# 8ChannelRebelSSR_v5.net
KiCad netlist of a schematic drawn in EAGLE
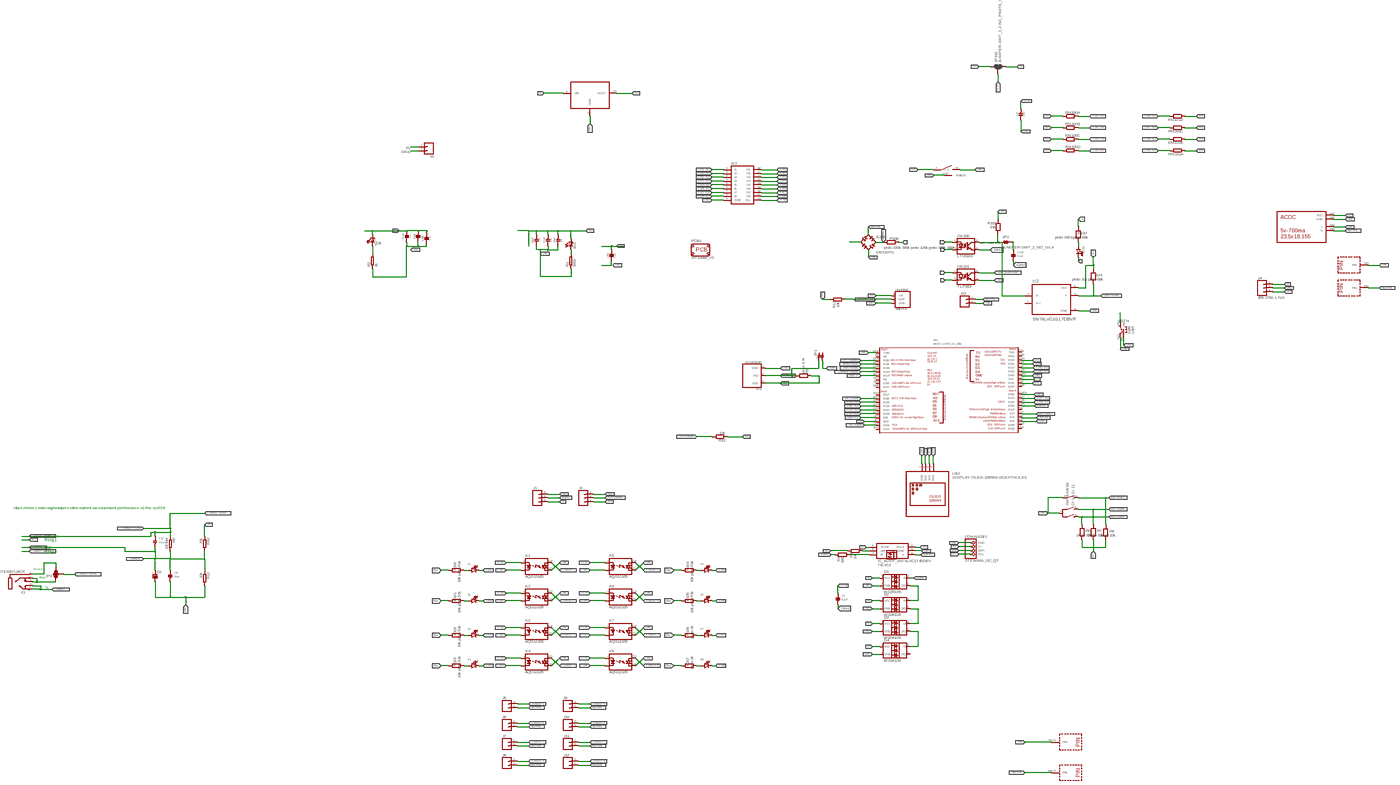
[diagram p0: schematic, sheet 1, overview]
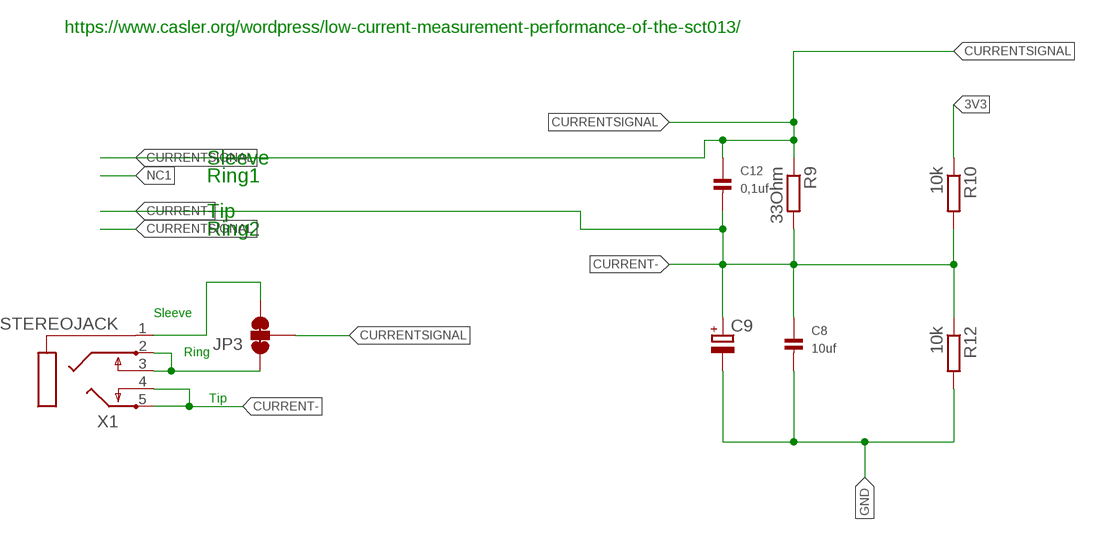
[diagram p1: schematic, sheet 1, part 1 of 4]
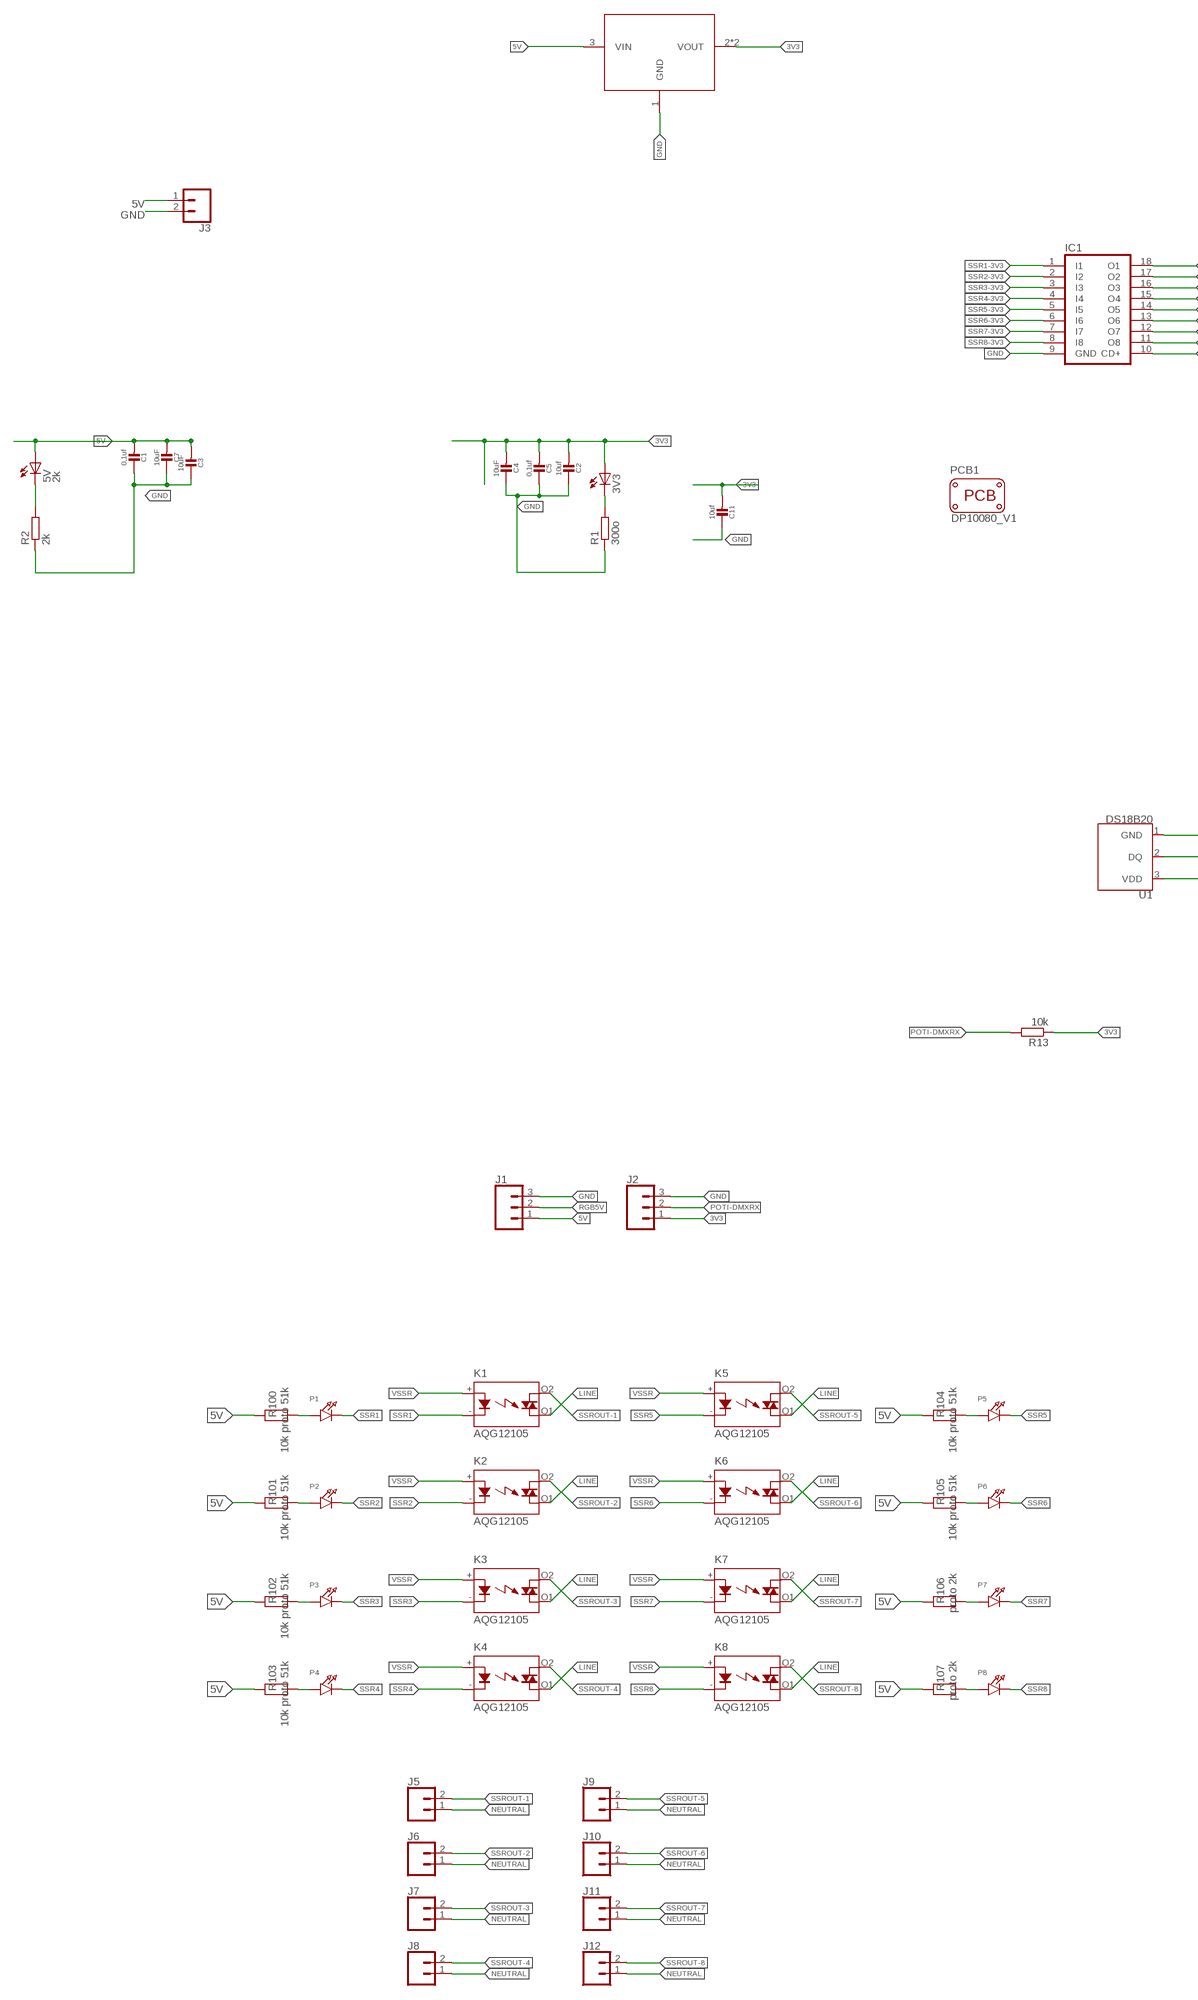
[diagram p2: schematic, sheet 1, part 2 of 4]
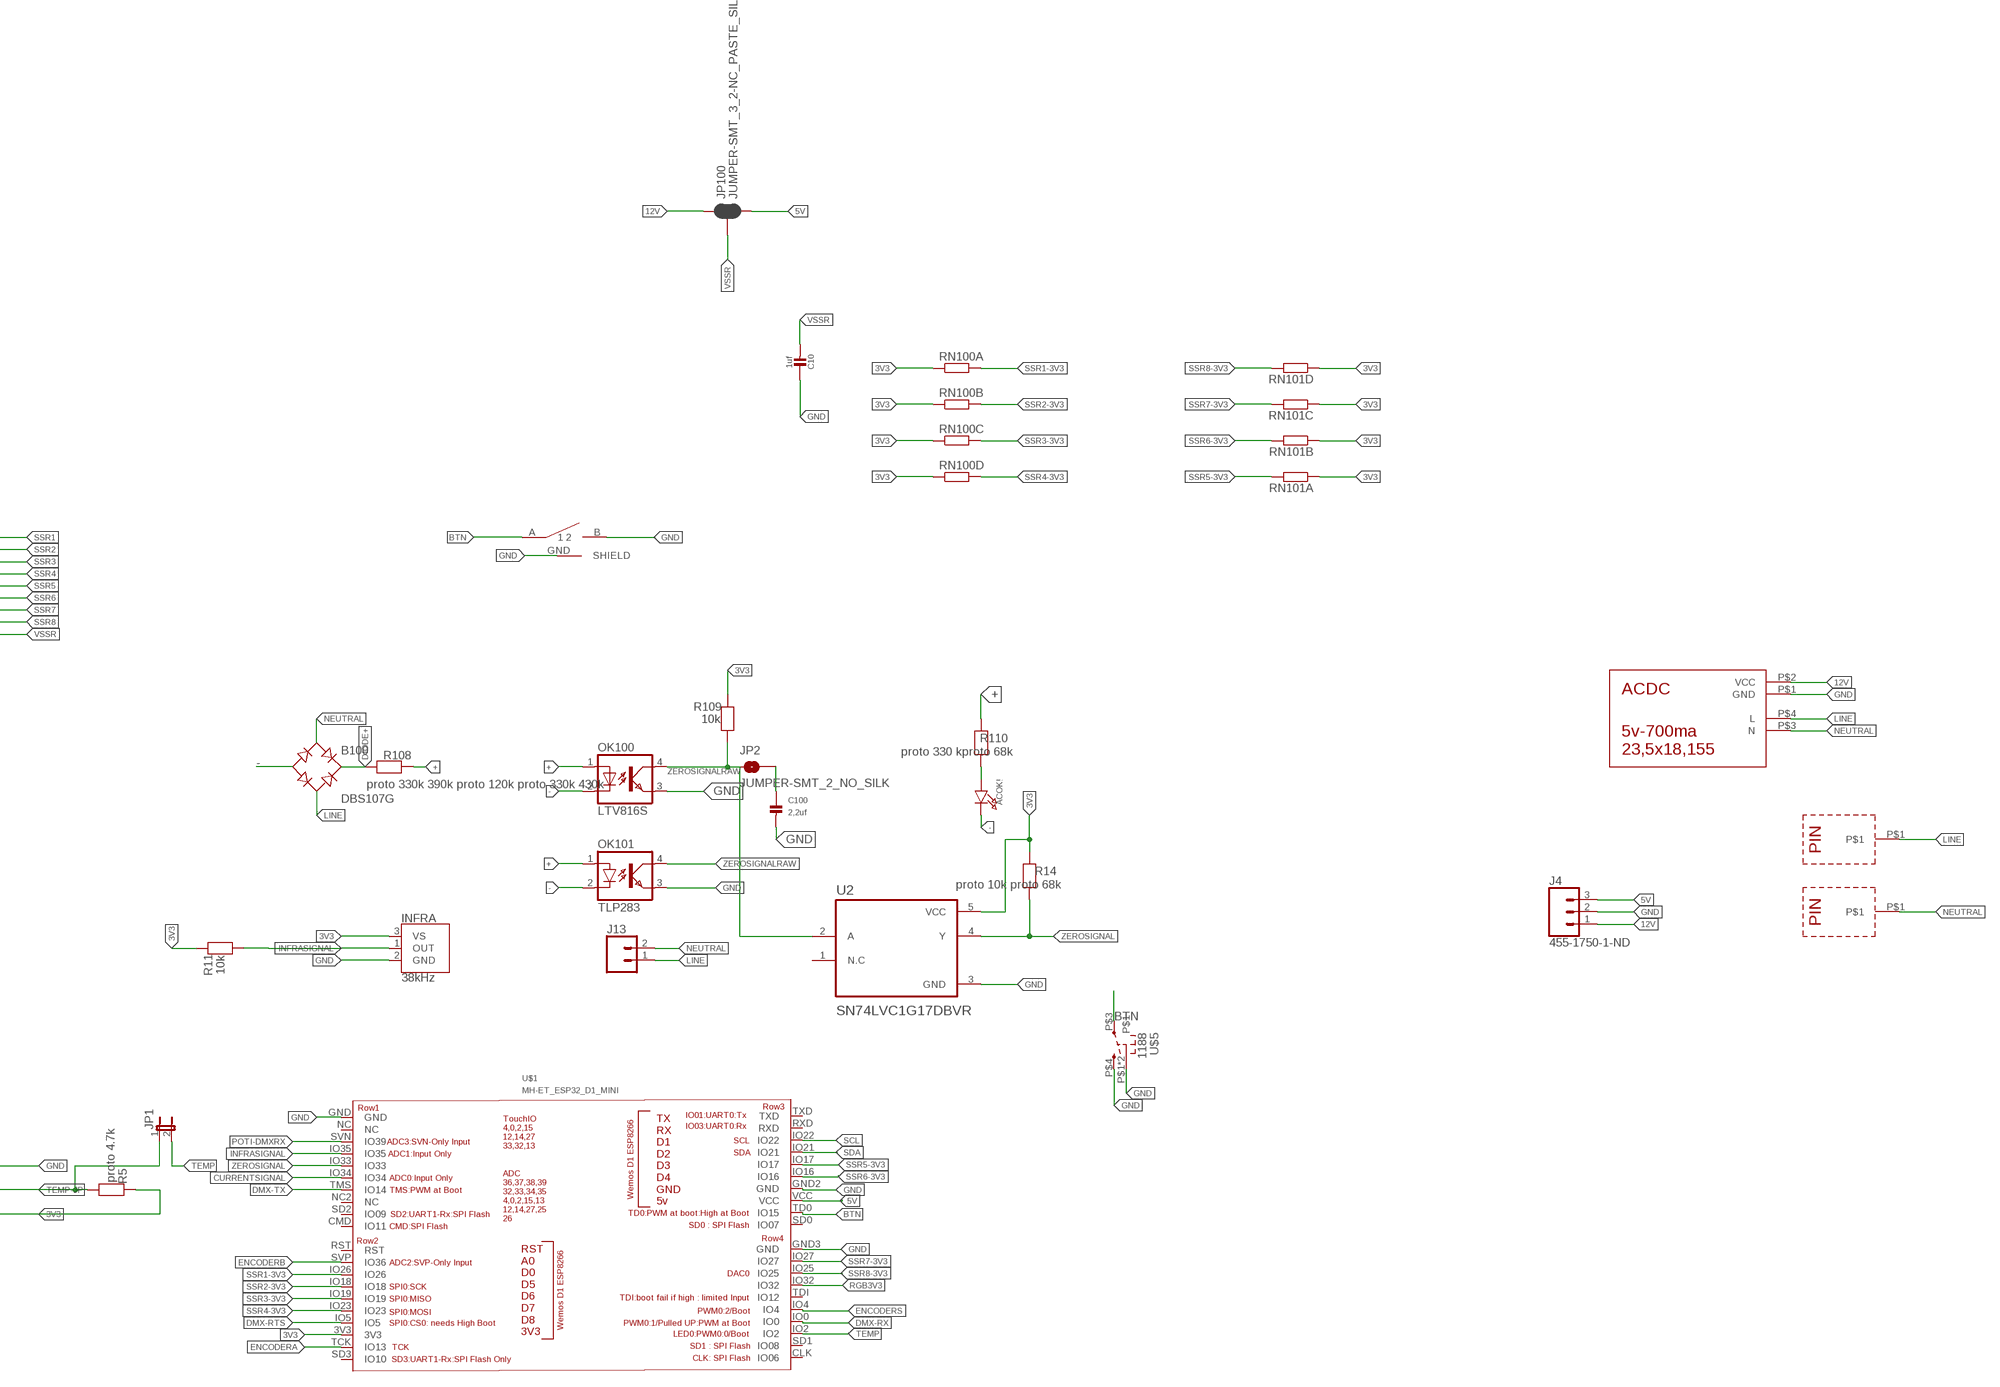
[diagram p3: schematic, sheet 1, part 3 of 4]
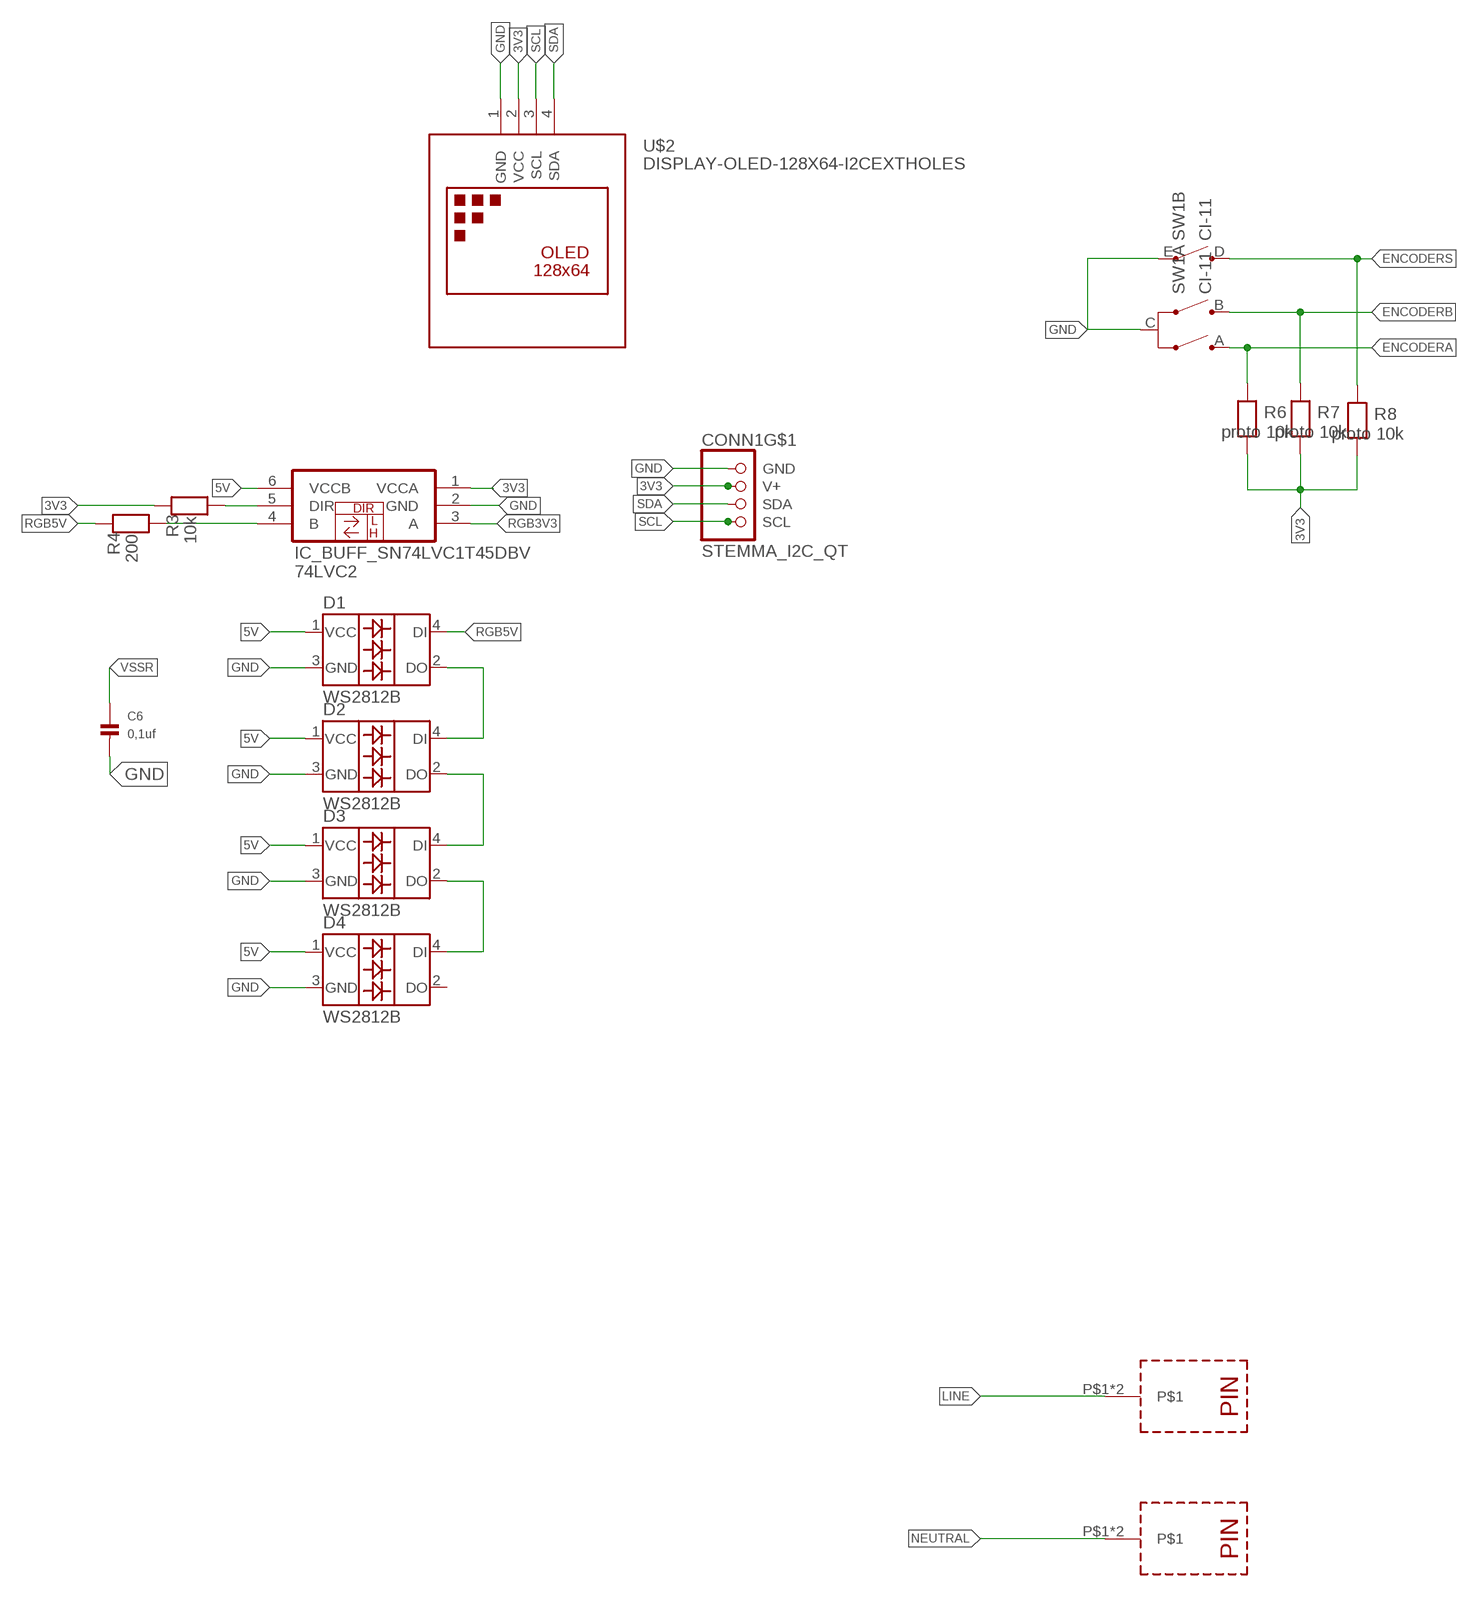
[diagram p4: schematic, sheet 1, part 4 of 4]

(export (version "E")
  (design (tool "Eeschema 10.0.6"))
  (components
    (comp (ref "3V3")
      (value "LEDCHIPLED_0805")
      (footprint "eagle-import:CHIPLED_0805")
      (libsource (lib "eagle-import") (part "LEDCHIPLED_0805"))
    )
    (comp (ref "5V")
      (value "2k")
      (footprint "eagle-import:CHIPLED_0805")
      (libsource (lib "eagle-import") (part "LEDCHIPLED_0805"))
    )
    (comp (ref "74LVC2")
      (value "IC_BUFF_SN74LVC1T45DBV")
      (footprint "eagle-import:DBV-R-PDSO-G6")
      (libsource (lib "eagle-import") (part "IC_BUFF_SN74LVC1T45DBV"))
    )
    (comp (ref "ACOK!")
      (value "LED0805")
      (footprint "eagle-import:CHIPLED_0805")
      (libsource (lib "eagle-import") (part "LED0805"))
    )
    (comp (ref "B100")
      (value "DBS107G")
      (footprint "eagle-import:DBS")
      (libsource (lib "eagle-import") (part "DB?GS107"))
    )
    (comp (ref "C1")
      (value "0,1uf")
      (footprint "eagle-import:0805-NO")
      (libsource (lib "eagle-import") (part "CAP_CERAMIC0805-NOOUTLINE"))
    )
    (comp (ref "C2")
      (value "10uf")
      (footprint "eagle-import:0805-NO")
      (libsource (lib "eagle-import") (part "CAP_CERAMIC0805-NOOUTLINE"))
    )
    (comp (ref "C3")
      (value "10uF")
      (footprint "eagle-import:0805-NO")
      (libsource (lib "eagle-import") (part "CAP_CERAMIC0805-NOOUTLINE"))
    )
    (comp (ref "C4")
      (value "10uF")
      (footprint "eagle-import:0805-NO")
      (libsource (lib "eagle-import") (part "CAP_CERAMIC0805-NOOUTLINE"))
    )
    (comp (ref "C5")
      (value "0,1uf")
      (footprint "eagle-import:0805-NO")
      (libsource (lib "eagle-import") (part "CAP_CERAMIC0805-NOOUTLINE"))
    )
    (comp (ref "C6")
      (value "0,1uf")
      (footprint "eagle-import:0805_NOTHERMALS@1")
      (libsource (lib "eagle-import") (part "CAP_CERAMIC0805-NOTHERMALS"))
    )
    (comp (ref "C7")
      (value "10uF")
      (footprint "eagle-import:0805-NO")
      (libsource (lib "eagle-import") (part "CAP_CERAMIC0805-NOOUTLINE"))
    )
    (comp (ref "C8")
      (value "10uf")
      (footprint "eagle-import:0805_NOTHERMALS@1")
      (libsource (lib "eagle-import") (part "CAP_CERAMIC0805-NOTHERMALS"))
    )
    (comp (ref "C9")
      (value "CPOL-EUE1.8-4")
      (footprint "eagle-import:E1,8-4")
      (libsource (lib "eagle-import") (part "CPOL-EUE1.8-4"))
    )
    (comp (ref "C10")
      (value "1uf")
      (footprint "eagle-import:0805-NO")
      (libsource (lib "eagle-import") (part "CAP_CERAMIC0805-NOOUTLINE"))
    )
    (comp (ref "C11")
      (value "10uf")
      (footprint "eagle-import:0805-NO")
      (libsource (lib "eagle-import") (part "CAP_CERAMIC0805-NOOUTLINE"))
    )
    (comp (ref "C12")
      (value "0,1uf")
      (footprint "eagle-import:0805_NOTHERMALS@1")
      (libsource (lib "eagle-import") (part "CAP_CERAMIC0805-NOTHERMALS"))
    )
    (comp (ref "C100")
      (value "2,2uf")
      (footprint "eagle-import:0805_NOTHERMALS@1")
      (libsource (lib "eagle-import") (part "CAP_CERAMIC0805-NOTHERMALS"))
    )
    (comp (ref "CONN1")
      (value "STEMMA_I2C_QT")
      (footprint "eagle-import:JST_SH4")
      (libsource (lib "eagle-import") (part "STEMMA_I2C_QT"))
    )
    (comp (ref "D1")
      (value "WS2812B")
      (footprint "eagle-import:WS2812B")
      (libsource (lib "eagle-import") (part "WS2812B"))
    )
    (comp (ref "D2")
      (value "WS2812B")
      (footprint "eagle-import:WS2812B")
      (libsource (lib "eagle-import") (part "WS2812B"))
    )
    (comp (ref "D3")
      (value "WS2812B")
      (footprint "eagle-import:WS2812B")
      (libsource (lib "eagle-import") (part "WS2812B"))
    )
    (comp (ref "D4")
      (value "WS2812B")
      (footprint "eagle-import:WS2812B")
      (libsource (lib "eagle-import") (part "WS2812B"))
    )
    (comp (ref "IC1")
      (value "IC_ULN2803ADW")
      (footprint "eagle-import:SO-18L")
      (libsource (lib "eagle-import") (part "IC_ULN2803ADW"))
    )
    (comp (ref "INFRA")
      (value "38kHz")
      (footprint "eagle-import:TSOP382")
      (libsource (lib "eagle-import") (part "TSOP38238"))
    )
    (comp (ref "J1")
      (value "CONN_03POLAR")
      (footprint "eagle-import:MOLEX-1X3")
      (libsource (lib "eagle-import") (part "CONN_03POLAR"))
    )
    (comp (ref "J2")
      (value "CONN_03POLAR")
      (footprint "eagle-import:MOLEX-1X3")
      (libsource (lib "eagle-import") (part "CONN_03POLAR"))
    )
    (comp (ref "J3")
      (value "CONN_02POLAR")
      (footprint "eagle-import:MOLEX-1X2")
      (libsource (lib "eagle-import") (part "CONN_02POLAR"))
    )
    (comp (ref "J4")
      (value "455-1750-1-ND")
      (footprint "eagle-import:1X03")
      (libsource (lib "eagle-import") (part "CONN_03"))
    )
    (comp (ref "J5")
      (value "CONN_023.5MM")
      (footprint "eagle-import:SCREWTERMINAL-3.5MM-2")
      (libsource (lib "eagle-import") (part "CONN_023.5MM"))
    )
    (comp (ref "J6")
      (value "CONN_023.5MM")
      (footprint "eagle-import:SCREWTERMINAL-3.5MM-2")
      (libsource (lib "eagle-import") (part "CONN_023.5MM"))
    )
    (comp (ref "J7")
      (value "CONN_023.5MM")
      (footprint "eagle-import:SCREWTERMINAL-3.5MM-2")
      (libsource (lib "eagle-import") (part "CONN_023.5MM"))
    )
    (comp (ref "J8")
      (value "CONN_023.5MM")
      (footprint "eagle-import:SCREWTERMINAL-3.5MM-2")
      (libsource (lib "eagle-import") (part "CONN_023.5MM"))
    )
    (comp (ref "J9")
      (value "CONN_023.5MM")
      (footprint "eagle-import:SCREWTERMINAL-3.5MM-2")
      (libsource (lib "eagle-import") (part "CONN_023.5MM"))
    )
    (comp (ref "J10")
      (value "CONN_023.5MM")
      (footprint "eagle-import:SCREWTERMINAL-3.5MM-2")
      (libsource (lib "eagle-import") (part "CONN_023.5MM"))
    )
    (comp (ref "J11")
      (value "CONN_023.5MM")
      (footprint "eagle-import:SCREWTERMINAL-3.5MM-2")
      (libsource (lib "eagle-import") (part "CONN_023.5MM"))
    )
    (comp (ref "J12")
      (value "CONN_023.5MM")
      (footprint "eagle-import:SCREWTERMINAL-3.5MM-2")
      (libsource (lib "eagle-import") (part "CONN_023.5MM"))
    )
    (comp (ref "J13")
      (value "CONN_023.5MM")
      (footprint "eagle-import:SCREWTERMINAL-3.5MM-2")
      (libsource (lib "eagle-import") (part "CONN_023.5MM"))
    )
    (comp (ref "JP1")
      (value "JUMPER2")
      (footprint "eagle-import:JUMPER2")
      (libsource (lib "eagle-import") (part "JUMPER2"))
    )
    (comp (ref "JP2")
      (value "JUMPER-SMT_2_NO_SILK")
      (footprint "eagle-import:SMT-JUMPER_2_NO_SILK")
      (libsource (lib "eagle-import") (part "JUMPER-SMT_2_NO_SILK"))
    )
    (comp (ref "JP3")
      (value "JUMPER-PAD-3-NC_BY_TRACE")
      (footprint "eagle-import:PAD-JUMPER-3-3OF3_NC_BY_TRACE_YES_SILK_FULL_BOX")
      (libsource (lib "eagle-import") (part "JUMPER-PAD-3-NC_BY_TRACE"))
    )
    (comp (ref "JP100")
      (value "JUMPER-SMT_3_2-NC_PASTE_SILK")
      (footprint "eagle-import:SMT-JUMPER_3_2-NC_PASTE_SILK")
      (libsource (lib "eagle-import") (part "JUMPER-SMT_3_2-NC_PASTE_SILK"))
    )
    (comp (ref "K1")
      (value "AQG12105")
      (footprint "eagle-import:AQG")
      (fields (field (name "MF") "AROMAT/ MATSUSHITA"))
      (libsource (lib "eagle-import") (part "AQG12105"))
    )
    (comp (ref "K2")
      (value "AQG12105")
      (footprint "eagle-import:AQG")
      (fields (field (name "MF") "AROMAT/ MATSUSHITA"))
      (libsource (lib "eagle-import") (part "AQG12105"))
    )
    (comp (ref "K3")
      (value "AQG12105")
      (footprint "eagle-import:AQG")
      (fields (field (name "MF") "AROMAT/ MATSUSHITA"))
      (libsource (lib "eagle-import") (part "AQG12105"))
    )
    (comp (ref "K4")
      (value "AQG12105")
      (footprint "eagle-import:AQG")
      (fields (field (name "MF") "AROMAT/ MATSUSHITA"))
      (libsource (lib "eagle-import") (part "AQG12105"))
    )
    (comp (ref "K5")
      (value "AQG12105")
      (footprint "eagle-import:AQG")
      (fields (field (name "MF") "AROMAT/ MATSUSHITA"))
      (libsource (lib "eagle-import") (part "AQG12105"))
    )
    (comp (ref "K6")
      (value "AQG12105")
      (footprint "eagle-import:AQG")
      (fields (field (name "MF") "AROMAT/ MATSUSHITA"))
      (libsource (lib "eagle-import") (part "AQG12105"))
    )
    (comp (ref "K7")
      (value "AQG12105")
      (footprint "eagle-import:AQG")
      (fields (field (name "MF") "AROMAT/ MATSUSHITA"))
      (libsource (lib "eagle-import") (part "AQG12105"))
    )
    (comp (ref "K8")
      (value "AQG12105")
      (footprint "eagle-import:AQG")
      (fields (field (name "MF") "AROMAT/ MATSUSHITA"))
      (libsource (lib "eagle-import") (part "AQG12105"))
    )
    (comp (ref "OK100")
      (value "LTV816S")
      (footprint "eagle-import:DIL4-SMD")
      (libsource (lib "eagle-import") (part "LTV816S"))
    )
    (comp (ref "OK101")
      (value "TLP283")
      (footprint "eagle-import:MINI-FLAT-4")
      (libsource (lib "eagle-import") (part "TLP283"))
    )
    (comp (ref "P1")
      (value "LED0805")
      (footprint "eagle-import:CHIPLED_0805")
      (libsource (lib "eagle-import") (part "LED0805"))
    )
    (comp (ref "P2")
      (value "LED0805")
      (footprint "eagle-import:CHIPLED_0805")
      (libsource (lib "eagle-import") (part "LED0805"))
    )
    (comp (ref "P3")
      (value "LED0805")
      (footprint "eagle-import:CHIPLED_0805")
      (libsource (lib "eagle-import") (part "LED0805"))
    )
    (comp (ref "P4")
      (value "LED0805")
      (footprint "eagle-import:CHIPLED_0805")
      (libsource (lib "eagle-import") (part "LED0805"))
    )
    (comp (ref "P5")
      (value "LED0805")
      (footprint "eagle-import:CHIPLED_0805")
      (libsource (lib "eagle-import") (part "LED0805"))
    )
    (comp (ref "P6")
      (value "LED0805")
      (footprint "eagle-import:CHIPLED_0805")
      (libsource (lib "eagle-import") (part "LED0805"))
    )
    (comp (ref "P7")
      (value "LED0805")
      (footprint "eagle-import:CHIPLED_0805")
      (libsource (lib "eagle-import") (part "LED0805"))
    )
    (comp (ref "P8")
      (value "LED0805")
      (footprint "eagle-import:CHIPLED_0805")
      (libsource (lib "eagle-import") (part "LED0805"))
    )
    (comp (ref "PCB1")
      (value "PCB_DP_RECTANGLE-80X100")
      (footprint "eagle-import:DP10080_V1")
      (fields (field (name "PCB_SIZE") "DP10080_V1"))
      (libsource (lib "eagle-import") (part "PCB_DP_RECTANGLE-80X100"))
    )
    (comp (ref "R1")
      (value "300o")
      (footprint "eagle-import:R805")
      (libsource (lib "eagle-import") (part "RESISTOR-0805R805"))
    )
    (comp (ref "R2")
      (value "2k")
      (footprint "eagle-import:R805")
      (libsource (lib "eagle-import") (part "RESISTOR-0805R805"))
    )
    (comp (ref "R3")
      (value "10k")
      (footprint "eagle-import:0805@1")
      (libsource (lib "eagle-import") (part "RESISTOR0805"))
    )
    (comp (ref "R4")
      (value "200")
      (footprint "eagle-import:0805@1")
      (libsource (lib "eagle-import") (part "RESISTOR0805"))
    )
    (comp (ref "R5")
      (value "proto 4.7k")
      (footprint "eagle-import:0805@1")
      (libsource (lib "eagle-import") (part "RESISTOR0805"))
    )
    (comp (ref "R6")
      (value "proto 10k")
      (footprint "eagle-import:0805@1")
      (libsource (lib "eagle-import") (part "RESISTOR0805"))
    )
    (comp (ref "R7")
      (value "proto 10k")
      (footprint "eagle-import:0805@1")
      (libsource (lib "eagle-import") (part "RESISTOR0805"))
    )
    (comp (ref "R8")
      (value "proto 10k")
      (footprint "eagle-import:0805@1")
      (libsource (lib "eagle-import") (part "RESISTOR0805"))
    )
    (comp (ref "R9")
      (value "33Ohm")
      (footprint "eagle-import:R805")
      (libsource (lib "eagle-import") (part "RESISTOR-0805R805"))
    )
    (comp (ref "R10")
      (value "10k")
      (footprint "eagle-import:R805")
      (libsource (lib "eagle-import") (part "RESISTOR-0805R805"))
    )
    (comp (ref "R11")
      (value "10k")
      (footprint "eagle-import:0805@1")
      (libsource (lib "eagle-import") (part "RESISTOR0805"))
    )
    (comp (ref "R12")
      (value "10k")
      (footprint "eagle-import:R805")
      (libsource (lib "eagle-import") (part "RESISTOR-0805R805"))
    )
    (comp (ref "R13")
      (value "10k")
      (footprint "eagle-import:R805")
      (libsource (lib "eagle-import") (part "RESISTOR-0805R805"))
    )
    (comp (ref "R14")
      (value "proto 10k proto 68k")
      (footprint "eagle-import:0805@1")
      (libsource (lib "eagle-import") (part "RESISTOR0805"))
    )
    (comp (ref "R100")
      (value "10k proto 51k")
      (footprint "eagle-import:0805@1")
      (libsource (lib "eagle-import") (part "RESISTOR0805"))
    )
    (comp (ref "R101")
      (value "10k proto 51k")
      (footprint "eagle-import:0805@1")
      (libsource (lib "eagle-import") (part "RESISTOR0805"))
    )
    (comp (ref "R102")
      (value "10k proto 51k")
      (footprint "eagle-import:0805@1")
      (libsource (lib "eagle-import") (part "RESISTOR0805"))
    )
    (comp (ref "R103")
      (value "10k proto 51k")
      (footprint "eagle-import:0805@1")
      (libsource (lib "eagle-import") (part "RESISTOR0805"))
    )
    (comp (ref "R104")
      (value "10k proto 51k")
      (footprint "eagle-import:0805@1")
      (libsource (lib "eagle-import") (part "RESISTOR0805"))
    )
    (comp (ref "R105")
      (value "10k proto 51k")
      (footprint "eagle-import:0805@1")
      (libsource (lib "eagle-import") (part "RESISTOR0805"))
    )
    (comp (ref "R106")
      (value "proto 2k")
      (footprint "eagle-import:0805@1")
      (libsource (lib "eagle-import") (part "RESISTOR0805"))
    )
    (comp (ref "R107")
      (value "proto 2k")
      (footprint "eagle-import:0805@1")
      (libsource (lib "eagle-import") (part "RESISTOR0805"))
    )
    (comp (ref "R108")
      (value "proto 330k 390k proto 120k proto 330k 430k")
      (footprint "eagle-import:0805@1")
      (libsource (lib "eagle-import") (part "RESISTOR0805"))
    )
    (comp (ref "R109")
      (value "10k")
      (footprint "eagle-import:0805@1")
      (libsource (lib "eagle-import") (part "RESISTOR0805"))
    )
    (comp (ref "R110")
      (value "proto 330 kproto 68k")
      (footprint "eagle-import:0805@1")
      (libsource (lib "eagle-import") (part "RESISTOR0805"))
    )
    (comp (ref "RN100")
      (value "RESISTOR_ARRAY_4")
      (footprint "eagle-import:RN8P-4R-CRA06S")
      (libsource (lib "eagle-import") (part "RESISTOR_ARRAY_4"))
    )
    (comp (ref "RN101")
      (value "RESISTOR_ARRAY_4")
      (footprint "eagle-import:RN8P-4R-CRA06S")
      (libsource (lib "eagle-import") (part "RESISTOR_ARRAY_4"))
    )
    (comp (ref "SW1")
      (value "CI-11")
      (footprint "eagle-import:CI-11")
      (libsource (lib "eagle-import") (part "CI-11"))
    )
    (comp (ref "U$1")
      (value "MH-ET_ESP32_D1_MINI")
      (footprint "eagle-import:MH-ET_ESP32_D1_MINI")
      (libsource (lib "eagle-import") (part "MH-ET_ESP32_D1_MINI"))
    )
    (comp (ref "U$2")
      (value "DISPLAY-OLED-128X64-I2CEXTHOLES")
      (footprint "eagle-import:DISPLAY-OLED-128X64-MAX-I2C")
      (libsource (lib "eagle-import") (part "DISPLAY-OLED-128X64-I2CEXTHOLES"))
    )
    (comp (ref "U$4")
      (value "SWITCH4.5-4,5")
      (footprint "eagle-import:SWITCH4.5X4.5")
      (libsource (lib "eagle-import") (part "SWITCH4.5-4,5"))
    )
    (comp (ref "U$5")
      (value "1188")
      (footprint "eagle-import:1188")
      (libsource (lib "eagle-import") (part "1188"))
    )
    (comp (ref "U$6")
      (value "AP11173V3")
      (footprint "eagle-import:SOT223")
      (libsource (lib "eagle-import") (part "AP11173V3"))
    )
    (comp (ref "U$7")
      (value "ACDC-SUPPLY")
      (footprint "eagle-import:ACDC-5V")
      (libsource (lib "eagle-import") (part "ACDC-SUPPLY"))
    )
    (comp (ref "U$15")
      (value "EST026_COLDPRESSTERMINAL")
      (footprint "eagle-import:EST026-COLDPRESSTERMINAL")
      (libsource (lib "eagle-import") (part "EST026_COLDPRESSTERMINAL"))
    )
    (comp (ref "U$16")
      (value "SCREWTERMINAL_BLOCL5X5_FLAT")
      (footprint "eagle-import:SCREWTERMINALFLAT5X5")
      (libsource (lib "eagle-import") (part "SCREWTERMINAL_BLOCL5X5_FLAT"))
    )
    (comp (ref "U$17")
      (value "EST026_COLDPRESSTERMINAL")
      (footprint "eagle-import:EST026-COLDPRESSTERMINAL")
      (libsource (lib "eagle-import") (part "EST026_COLDPRESSTERMINAL"))
    )
    (comp (ref "U$18")
      (value "SCREWTERMINAL_BLOCL5X5_FLAT")
      (footprint "eagle-import:SCREWTERMINALFLAT5X5")
      (libsource (lib "eagle-import") (part "SCREWTERMINAL_BLOCL5X5_FLAT"))
    )
    (comp (ref "U1")
      (value "DS18B20")
      (footprint "eagle-import:TO-92-AMMO")
      (libsource (lib "eagle-import") (part "DS18B20"))
    )
    (comp (ref "U2")
      (value "SN74LVC1G17DBVR")
      (footprint "eagle-import:SOT95P280X145-5N")
      (fields (field (name "MF") "Texas Instruments"))
      (libsource (lib "eagle-import") (part "SN74LVC1G17DBVR"))
    )
    (comp (ref "X1")
      (value "STEREOJACK")
      (footprint "eagle-import:STX3100")
      (libsource (lib "eagle-import") (part "STEREOJACK"))
    )
  )
  (nets
    (net (code "1") (name "+") (class "Default")
      (node (ref "OK100") (pin "1") (pinfunction "A_1") (pintype "passive"))
      (node (ref "OK101") (pin "1") (pinfunction "A_1") (pintype "passive"))
      (node (ref "R108") (pin "2") (pinfunction "2_2") (pintype "passive"))
      (node (ref "R110") (pin "2") (pinfunction "2_2") (pintype "passive"))
    )
    (net (code "2") (name "-") (class "Default")
      (node (ref "ACOK!") (pin "C") (pinfunction "C_C") (pintype "passive"))
      (node (ref "B100") (pin "-") (pinfunction "-_-") (pintype "passive"))
      (node (ref "OK100") (pin "2") (pinfunction "C_2") (pintype "passive"))
      (node (ref "OK101") (pin "2") (pinfunction "C_2") (pintype "passive"))
    )
    (net (code "3") (name "3V3") (class "Default")
      (node (ref "3V3") (pin "A") (pinfunction "A_A") (pintype "passive"))
      (node (ref "74LVC2") (pin "1") (pinfunction "VCCA_1") (pintype "power_in"))
      (node (ref "C11") (pin "2") (pinfunction "2_2") (pintype "passive"))
      (node (ref "C2") (pin "2") (pinfunction "2_2") (pintype "passive"))
      (node (ref "C4") (pin "2") (pinfunction "2_2") (pintype "passive"))
      (node (ref "C5") (pin "2") (pinfunction "2_2") (pintype "passive"))
      (node (ref "CONN1") (pin "2") (pinfunction "V+_2") (pintype "passive"))
      (node (ref "INFRA") (pin "3") (pinfunction "VS_3") (pintype "bidirectional"))
      (node (ref "J2") (pin "1") (pinfunction "1_1") (pintype "passive"))
      (node (ref "R10") (pin "1") (pinfunction "1_1") (pintype "passive"))
      (node (ref "R109") (pin "2") (pinfunction "2_2") (pintype "passive"))
      (node (ref "R11") (pin "2") (pinfunction "2_2") (pintype "passive"))
      (node (ref "R13") (pin "1") (pinfunction "1_1") (pintype "passive"))
      (node (ref "R14") (pin "2") (pinfunction "2_2") (pintype "passive"))
      (node (ref "R3") (pin "2") (pinfunction "2_2") (pintype "passive"))
      (node (ref "R5") (pin "2") (pinfunction "2_2") (pintype "passive"))
      (node (ref "R6") (pin "1") (pinfunction "1_1") (pintype "passive"))
      (node (ref "R7") (pin "1") (pinfunction "1_1") (pintype "passive"))
      (node (ref "R8") (pin "1") (pinfunction "1_1") (pintype "passive"))
      (node (ref "RN100") (pin "1") (pinfunction "1_1") (pintype "passive"))
      (node (ref "RN100") (pin "2") (pinfunction "1_2") (pintype "passive"))
      (node (ref "RN100") (pin "3") (pinfunction "1_3") (pintype "passive"))
      (node (ref "RN100") (pin "4") (pinfunction "1_4") (pintype "passive"))
      (node (ref "RN101") (pin "1") (pinfunction "1_1") (pintype "passive"))
      (node (ref "RN101") (pin "2") (pinfunction "1_2") (pintype "passive"))
      (node (ref "RN101") (pin "3") (pinfunction "1_3") (pintype "passive"))
      (node (ref "RN101") (pin "4") (pinfunction "1_4") (pintype "passive"))
      (node (ref "U$1") (pin "3V3") (pinfunction "3V3_3V3") (pintype "bidirectional"))
      (node (ref "U$2") (pin "2") (pinfunction "VCC_2") (pintype "power_in"))
      (node (ref "U$6") (pin "2") (pinfunction "VOUT_2") (pintype "bidirectional"))
      (node (ref "U$6") (pin "4") (pinfunction "VOUT_4") (pintype "bidirectional"))
      (node (ref "U1") (pin "3") (pinfunction "VDD_3") (pintype "power_in"))
      (node (ref "U2") (pin "5") (pinfunction "VCC_5") (pintype "power_in"))
    )
    (net (code "4") (name "5V") (class "Default")
      (node (ref "5V") (pin "A") (pinfunction "A_A") (pintype "passive"))
      (node (ref "74LVC2") (pin "6") (pinfunction "VCCB_6") (pintype "power_in"))
      (node (ref "C1") (pin "2") (pinfunction "2_2") (pintype "passive"))
      (node (ref "C3") (pin "2") (pinfunction "2_2") (pintype "passive"))
      (node (ref "C7") (pin "2") (pinfunction "2_2") (pintype "passive"))
      (node (ref "D1") (pin "1") (pinfunction "VCC_1") (pintype "power_in"))
      (node (ref "D2") (pin "1") (pinfunction "VCC_1") (pintype "power_in"))
      (node (ref "D3") (pin "1") (pinfunction "VCC_1") (pintype "power_in"))
      (node (ref "D4") (pin "1") (pinfunction "VCC_1") (pintype "power_in"))
      (node (ref "J1") (pin "1") (pinfunction "1_1") (pintype "passive"))
      (node (ref "J3") (pin "1") (pinfunction "1_1") (pintype "passive"))
      (node (ref "J4") (pin "3") (pinfunction "3_3") (pintype "passive"))
      (node (ref "JP100") (pin "3") (pinfunction "3_3") (pintype "passive"))
      (node (ref "R100") (pin "2") (pinfunction "2_2") (pintype "passive"))
      (node (ref "R101") (pin "2") (pinfunction "2_2") (pintype "passive"))
      (node (ref "R102") (pin "2") (pinfunction "2_2") (pintype "passive"))
      (node (ref "R103") (pin "2") (pinfunction "2_2") (pintype "passive"))
      (node (ref "R104") (pin "2") (pinfunction "2_2") (pintype "passive"))
      (node (ref "R105") (pin "2") (pinfunction "2_2") (pintype "passive"))
      (node (ref "R106") (pin "2") (pinfunction "2_2") (pintype "passive"))
      (node (ref "R107") (pin "2") (pinfunction "2_2") (pintype "passive"))
      (node (ref "U$1") (pin "VCC") (pinfunction "VCC_VCC") (pintype "bidirectional"))
      (node (ref "U$6") (pin "3") (pinfunction "VIN_3") (pintype "bidirectional"))
    )
    (net (code "5") (name "12V") (class "Default")
      (node (ref "J4") (pin "1") (pinfunction "1_1") (pintype "passive"))
      (node (ref "JP100") (pin "1") (pinfunction "1_1") (pintype "passive"))
      (node (ref "U$7") (pin "P$2") (pinfunction "VCC_P$2") (pintype "bidirectional"))
    )
    (net (code "6") (name "BTN") (class "Default")
      (node (ref "U$1") (pin "TD0") (pinfunction "IO15_TD0") (pintype "bidirectional"))
      (node (ref "U$4") (pin "A") (pinfunction "1_A") (pintype "bidirectional"))
      (node (ref "U$5") (pin "P$3") (pinfunction "1_P$3") (pintype "passive"))
    )
    (net (code "7") (name "CURRENT-") (class "Default")
      (node (ref "C12") (pin "2") (pinfunction "2_2") (pintype "passive"))
      (node (ref "C8") (pin "1") (pinfunction "1_1") (pintype "passive"))
      (node (ref "C9") (pin "+") (pinfunction "+_+") (pintype "passive"))
      (node (ref "R10") (pin "2") (pinfunction "2_2") (pintype "passive"))
      (node (ref "R12") (pin "1") (pinfunction "1_1") (pintype "passive"))
      (node (ref "R9") (pin "2") (pinfunction "2_2") (pintype "passive"))
      (node (ref "X1") (pin "4") (pinfunction "4_4") (pintype "passive"))
      (node (ref "X1") (pin "5") (pinfunction "5_5") (pintype "passive"))
    )
    (net (code "8") (name "CURRENTSIGNAL") (class "Default")
      (node (ref "C12") (pin "1") (pinfunction "1_1") (pintype "passive"))
      (node (ref "JP3") (pin "2") (pinfunction "2_2") (pintype "passive"))
      (node (ref "R9") (pin "1") (pinfunction "1_1") (pintype "passive"))
      (node (ref "U$1") (pin "IO34") (pinfunction "IO34_IO34") (pintype "bidirectional"))
    )
    (net (code "9") (name "DIODE+") (class "Default")
      (node (ref "B100") (pin "+") (pinfunction "+_+") (pintype "passive"))
      (node (ref "R108") (pin "1") (pinfunction "1_1") (pintype "passive"))
    )
    (net (code "10") (name "DMX-RTS") (class "Default")
      (node (ref "U$1") (pin "IO5") (pinfunction "IO5_IO5") (pintype "bidirectional"))
    )
    (net (code "11") (name "DMX-RX") (class "Default")
      (node (ref "U$1") (pin "IO0") (pinfunction "IO0_IO0") (pintype "bidirectional"))
    )
    (net (code "12") (name "DMX-TX") (class "Default")
      (node (ref "U$1") (pin "TMS") (pinfunction "IO14_TMS") (pintype "bidirectional"))
    )
    (net (code "13") (name "ENCODERA") (class "Default")
      (node (ref "R6") (pin "2") (pinfunction "2_2") (pintype "passive"))
      (node (ref "SW1") (pin "A") (pinfunction "A_A") (pintype "passive"))
      (node (ref "U$1") (pin "TCK") (pinfunction "IO13_TCK") (pintype "bidirectional"))
    )
    (net (code "14") (name "ENCODERB") (class "Default")
      (node (ref "R7") (pin "2") (pinfunction "2_2") (pintype "passive"))
      (node (ref "SW1") (pin "B") (pinfunction "B_B") (pintype "passive"))
      (node (ref "U$1") (pin "SVP") (pinfunction "IO36_SVP") (pintype "bidirectional"))
    )
    (net (code "15") (name "ENCODERS") (class "Default")
      (node (ref "R8") (pin "2") (pinfunction "2_2") (pintype "passive"))
      (node (ref "SW1") (pin "D") (pinfunction "D_D") (pintype "passive"))
      (node (ref "U$1") (pin "IO4") (pinfunction "IO4_IO4") (pintype "bidirectional"))
    )
    (net (code "16") (name "GND") (class "Default")
      (node (ref "74LVC2") (pin "2") (pinfunction "GND_2") (pintype "power_in"))
      (node (ref "C1") (pin "1") (pinfunction "1_1") (pintype "passive"))
      (node (ref "C10") (pin "1") (pinfunction "1_1") (pintype "passive"))
      (node (ref "C100") (pin "2") (pinfunction "2_2") (pintype "passive"))
      (node (ref "C11") (pin "1") (pinfunction "1_1") (pintype "passive"))
      (node (ref "C2") (pin "1") (pinfunction "1_1") (pintype "passive"))
      (node (ref "C3") (pin "1") (pinfunction "1_1") (pintype "passive"))
      (node (ref "C4") (pin "1") (pinfunction "1_1") (pintype "passive"))
      (node (ref "C5") (pin "1") (pinfunction "1_1") (pintype "passive"))
      (node (ref "C6") (pin "2") (pinfunction "2_2") (pintype "passive"))
      (node (ref "C7") (pin "1") (pinfunction "1_1") (pintype "passive"))
      (node (ref "C8") (pin "2") (pinfunction "2_2") (pintype "passive"))
      (node (ref "C9") (pin "-") (pinfunction "-_-") (pintype "passive"))
      (node (ref "CONN1") (pin "1") (pinfunction "GND_1") (pintype "passive"))
      (node (ref "D1") (pin "3") (pinfunction "GND_3") (pintype "power_in"))
      (node (ref "D2") (pin "3") (pinfunction "GND_3") (pintype "power_in"))
      (node (ref "D3") (pin "3") (pinfunction "GND_3") (pintype "power_in"))
      (node (ref "D4") (pin "3") (pinfunction "GND_3") (pintype "power_in"))
      (node (ref "IC1") (pin "9") (pinfunction "GND_9") (pintype "power_in"))
      (node (ref "INFRA") (pin "2") (pinfunction "GND_2") (pintype "bidirectional"))
      (node (ref "J1") (pin "3") (pinfunction "3_3") (pintype "passive"))
      (node (ref "J2") (pin "3") (pinfunction "3_3") (pintype "passive"))
      (node (ref "J3") (pin "2") (pinfunction "2_2") (pintype "passive"))
      (node (ref "J4") (pin "2") (pinfunction "2_2") (pintype "passive"))
      (node (ref "OK100") (pin "3") (pinfunction "EMIT_3") (pintype "passive"))
      (node (ref "OK101") (pin "3") (pinfunction "EMIT_3") (pintype "passive"))
      (node (ref "R1") (pin "1") (pinfunction "1_1") (pintype "passive"))
      (node (ref "R12") (pin "2") (pinfunction "2_2") (pintype "passive"))
      (node (ref "R2") (pin "1") (pinfunction "1_1") (pintype "passive"))
      (node (ref "SW1") (pin "C") (pinfunction "C_C") (pintype "passive"))
      (node (ref "SW1") (pin "E") (pinfunction "E_E") (pintype "passive"))
      (node (ref "U$1") (pin "GND") (pinfunction "GND_GND") (pintype "bidirectional"))
      (node (ref "U$1") (pin "GND2") (pinfunction "GND_GND2") (pintype "bidirectional"))
      (node (ref "U$1") (pin "GND3") (pinfunction "GND_GND3") (pintype "bidirectional"))
      (node (ref "U$2") (pin "1") (pinfunction "GND_1") (pintype "power_in"))
      (node (ref "U$4") (pin "B") (pinfunction "2_B") (pintype "bidirectional"))
      (node (ref "U$4") (pin "GND") (pinfunction "SHIELD_GND") (pintype "bidirectional"))
      (node (ref "U$5") (pin "P$1") (pinfunction "P$1_P$1") (pintype "bidirectional"))
      (node (ref "U$5") (pin "P$2") (pinfunction "P$1_P$2") (pintype "bidirectional"))
      (node (ref "U$5") (pin "P$4") (pinfunction "3_P$4") (pintype "passive"))
      (node (ref "U$6") (pin "1") (pinfunction "GND_1") (pintype "bidirectional"))
      (node (ref "U$7") (pin "P$1") (pinfunction "GND_P$1") (pintype "bidirectional"))
      (node (ref "U1") (pin "1") (pinfunction "GND_1") (pintype "power_in"))
      (node (ref "U2") (pin "3") (pinfunction "GND_3") (pintype "power_in"))
    )
    (net (code "17") (name "INFRASIGNAL") (class "Default")
      (node (ref "INFRA") (pin "1") (pinfunction "OUT_1") (pintype "bidirectional"))
      (node (ref "R11") (pin "1") (pinfunction "1_1") (pintype "passive"))
      (node (ref "U$1") (pin "IO35") (pinfunction "IO35_IO35") (pintype "bidirectional"))
    )
    (net (code "18") (name "LINE") (class "Default")
      (node (ref "B100") (pin "AC2") (pinfunction "AC2_AC2") (pintype "passive"))
      (node (ref "J13") (pin "1") (pinfunction "1_1") (pintype "passive"))
      (node (ref "K1") (pin "O1") (pinfunction "DS2_O1") (pintype "passive"))
      (node (ref "K2") (pin "O1") (pinfunction "DS2_O1") (pintype "passive"))
      (node (ref "K3") (pin "O1") (pinfunction "DS2_O1") (pintype "passive"))
      (node (ref "K4") (pin "O1") (pinfunction "DS2_O1") (pintype "passive"))
      (node (ref "K5") (pin "O1") (pinfunction "DS2_O1") (pintype "passive"))
      (node (ref "K6") (pin "O1") (pinfunction "DS2_O1") (pintype "passive"))
      (node (ref "K7") (pin "O1") (pinfunction "DS2_O1") (pintype "passive"))
      (node (ref "K8") (pin "O1") (pinfunction "DS2_O1") (pintype "passive"))
      (node (ref "U$15") (pin "P$1") (pinfunction "P$1_P$1") (pintype "bidirectional"))
      (node (ref "U$15") (pin "P$2") (pinfunction "P$1_P$2") (pintype "bidirectional"))
      (node (ref "U$16") (pin "P$1") (pinfunction "P$1_P$1") (pintype "bidirectional"))
      (node (ref "U$7") (pin "P$4") (pinfunction "L_P$4") (pintype "bidirectional"))
    )
    (net (code "20") (name "NEUTRAL") (class "Default")
      (node (ref "B100") (pin "AC1") (pinfunction "AC1_AC1") (pintype "passive"))
      (node (ref "J10") (pin "1") (pinfunction "1_1") (pintype "passive"))
      (node (ref "J11") (pin "1") (pinfunction "1_1") (pintype "passive"))
      (node (ref "J12") (pin "1") (pinfunction "1_1") (pintype "passive"))
      (node (ref "J13") (pin "2") (pinfunction "2_2") (pintype "passive"))
      (node (ref "J5") (pin "1") (pinfunction "1_1") (pintype "passive"))
      (node (ref "J6") (pin "1") (pinfunction "1_1") (pintype "passive"))
      (node (ref "J7") (pin "1") (pinfunction "1_1") (pintype "passive"))
      (node (ref "J8") (pin "1") (pinfunction "1_1") (pintype "passive"))
      (node (ref "J9") (pin "1") (pinfunction "1_1") (pintype "passive"))
      (node (ref "U$17") (pin "P$1") (pinfunction "P$1_P$1") (pintype "bidirectional"))
      (node (ref "U$17") (pin "P$2") (pinfunction "P$1_P$2") (pintype "bidirectional"))
      (node (ref "U$18") (pin "P$1") (pinfunction "P$1_P$1") (pintype "bidirectional"))
      (node (ref "U$7") (pin "P$3") (pinfunction "N_P$3") (pintype "bidirectional"))
    )
    (net (code "21") (name "Net-(3V3-PadC)") (class "Default")
      (node (ref "3V3") (pin "C") (pinfunction "C_C") (pintype "passive"))
      (node (ref "R1") (pin "2") (pinfunction "2_2") (pintype "passive"))
    )
    (net (code "22") (name "Net-(5V-PadC)") (class "Default")
      (node (ref "5V") (pin "C") (pinfunction "C_C") (pintype "passive"))
      (node (ref "R2") (pin "2") (pinfunction "2_2") (pintype "passive"))
    )
    (net (code "23") (name "Net-(74LVC2-B)") (class "Default")
      (node (ref "74LVC2") (pin "4") (pinfunction "B_4") (pintype "bidirectional"))
      (node (ref "R4") (pin "1") (pinfunction "1_1") (pintype "passive"))
    )
    (net (code "24") (name "Net-(74LVC2-DIR)") (class "Default")
      (node (ref "74LVC2") (pin "5") (pinfunction "DIR_5") (pintype "input"))
      (node (ref "R3") (pin "1") (pinfunction "1_1") (pintype "passive"))
    )
    (net (code "25") (name "Net-(ACOK!-PadA)") (class "Default")
      (node (ref "ACOK!") (pin "A") (pinfunction "A_A") (pintype "passive"))
      (node (ref "R110") (pin "1") (pinfunction "1_1") (pintype "passive"))
    )
    (net (code "26") (name "Net-(C100-Pad1)") (class "Default")
      (node (ref "C100") (pin "1") (pinfunction "1_1") (pintype "passive"))
      (node (ref "JP2") (pin "2") (pinfunction "2_2") (pintype "passive"))
    )
    (net (code "27") (name "Net-(D1-DO)") (class "Default")
      (node (ref "D1") (pin "2") (pinfunction "DO_2") (pintype "bidirectional"))
      (node (ref "D2") (pin "4") (pinfunction "DI_4") (pintype "bidirectional"))
    )
    (net (code "28") (name "Net-(D2-DO)") (class "Default")
      (node (ref "D2") (pin "2") (pinfunction "DO_2") (pintype "bidirectional"))
      (node (ref "D3") (pin "4") (pinfunction "DI_4") (pintype "bidirectional"))
    )
    (net (code "29") (name "Net-(D3-DO)") (class "Default")
      (node (ref "D3") (pin "2") (pinfunction "DO_2") (pintype "bidirectional"))
      (node (ref "D4") (pin "4") (pinfunction "DI_4") (pintype "bidirectional"))
    )
    (net (code "30") (name "Net-(JP3-Pad1)") (class "Default")
      (node (ref "JP3") (pin "1") (pinfunction "1_1") (pintype "passive"))
      (node (ref "X1") (pin "2") (pinfunction "2_2") (pintype "passive"))
      (node (ref "X1") (pin "3") (pinfunction "3_3") (pintype "passive"))
    )
    (net (code "31") (name "Net-(JP3-Pad3)") (class "Default")
      (node (ref "JP3") (pin "3") (pinfunction "3_3") (pintype "passive"))
      (node (ref "X1") (pin "1") (pinfunction "1_1") (pintype "passive"))
    )
    (net (code "32") (name "Net-(P1-PadA)") (class "Default")
      (node (ref "P1") (pin "A") (pinfunction "A_A") (pintype "passive"))
      (node (ref "R100") (pin "1") (pinfunction "1_1") (pintype "passive"))
    )
    (net (code "33") (name "Net-(P2-PadA)") (class "Default")
      (node (ref "P2") (pin "A") (pinfunction "A_A") (pintype "passive"))
      (node (ref "R101") (pin "1") (pinfunction "1_1") (pintype "passive"))
    )
    (net (code "34") (name "Net-(P3-PadA)") (class "Default")
      (node (ref "P3") (pin "A") (pinfunction "A_A") (pintype "passive"))
      (node (ref "R102") (pin "1") (pinfunction "1_1") (pintype "passive"))
    )
    (net (code "35") (name "Net-(P4-PadA)") (class "Default")
      (node (ref "P4") (pin "A") (pinfunction "A_A") (pintype "passive"))
      (node (ref "R103") (pin "1") (pinfunction "1_1") (pintype "passive"))
    )
    (net (code "36") (name "Net-(P5-PadA)") (class "Default")
      (node (ref "P5") (pin "A") (pinfunction "A_A") (pintype "passive"))
      (node (ref "R104") (pin "1") (pinfunction "1_1") (pintype "passive"))
    )
    (net (code "37") (name "Net-(P6-PadA)") (class "Default")
      (node (ref "P6") (pin "A") (pinfunction "A_A") (pintype "passive"))
      (node (ref "R105") (pin "1") (pinfunction "1_1") (pintype "passive"))
    )
    (net (code "38") (name "Net-(P7-PadA)") (class "Default")
      (node (ref "P7") (pin "A") (pinfunction "A_A") (pintype "passive"))
      (node (ref "R106") (pin "1") (pinfunction "1_1") (pintype "passive"))
    )
    (net (code "39") (name "Net-(P8-PadA)") (class "Default")
      (node (ref "P8") (pin "A") (pinfunction "A_A") (pintype "passive"))
      (node (ref "R107") (pin "1") (pinfunction "1_1") (pintype "passive"))
    )
    (net (code "40") (name "POTI-DMXRX") (class "Default")
      (node (ref "J2") (pin "2") (pinfunction "2_2") (pintype "passive"))
      (node (ref "R13") (pin "2") (pinfunction "2_2") (pintype "passive"))
      (node (ref "U$1") (pin "SVN") (pinfunction "IO39_SVN") (pintype "bidirectional"))
    )
    (net (code "41") (name "RGB3V3") (class "Default")
      (node (ref "74LVC2") (pin "3") (pinfunction "A_3") (pintype "bidirectional"))
      (node (ref "U$1") (pin "IO32") (pinfunction "IO32_IO32") (pintype "bidirectional"))
    )
    (net (code "42") (name "RGB5V") (class "Default")
      (node (ref "D1") (pin "4") (pinfunction "DI_4") (pintype "bidirectional"))
      (node (ref "J1") (pin "2") (pinfunction "2_2") (pintype "passive"))
      (node (ref "R4") (pin "2") (pinfunction "2_2") (pintype "passive"))
    )
    (net (code "43") (name "SCL") (class "Default")
      (node (ref "CONN1") (pin "4") (pinfunction "SCL_4") (pintype "passive"))
      (node (ref "U$1") (pin "IO22") (pinfunction "IO22_IO22") (pintype "bidirectional"))
      (node (ref "U$2") (pin "3") (pinfunction "SCL_3") (pintype "bidirectional"))
    )
    (net (code "44") (name "SDA") (class "Default")
      (node (ref "CONN1") (pin "3") (pinfunction "SDA_3") (pintype "passive"))
      (node (ref "U$1") (pin "IO21") (pinfunction "IO21_IO21") (pintype "bidirectional"))
      (node (ref "U$2") (pin "4") (pinfunction "SDA_4") (pintype "bidirectional"))
    )
    (net (code "45") (name "SSR1") (class "Default")
      (node (ref "IC1") (pin "18") (pinfunction "O1_18") (pintype "open_collector"))
      (node (ref "K1") (pin "-") (pinfunction "K_-") (pintype "passive"))
      (node (ref "P1") (pin "C") (pinfunction "C_C") (pintype "passive"))
    )
    (net (code "46") (name "SSR1-3V3") (class "Default")
      (node (ref "IC1") (pin "1") (pinfunction "I1_1") (pintype "input"))
      (node (ref "RN100") (pin "8") (pinfunction "2_8") (pintype "passive"))
      (node (ref "U$1") (pin "IO26") (pinfunction "IO26_IO26") (pintype "bidirectional"))
    )
    (net (code "47") (name "SSR2") (class "Default")
      (node (ref "IC1") (pin "17") (pinfunction "O2_17") (pintype "open_collector"))
      (node (ref "K2") (pin "-") (pinfunction "K_-") (pintype "passive"))
      (node (ref "P2") (pin "C") (pinfunction "C_C") (pintype "passive"))
    )
    (net (code "48") (name "SSR2-3V3") (class "Default")
      (node (ref "IC1") (pin "2") (pinfunction "I2_2") (pintype "input"))
      (node (ref "RN100") (pin "7") (pinfunction "2_7") (pintype "passive"))
      (node (ref "U$1") (pin "IO18") (pinfunction "IO18_IO18") (pintype "bidirectional"))
    )
    (net (code "49") (name "SSR3") (class "Default")
      (node (ref "IC1") (pin "16") (pinfunction "O3_16") (pintype "open_collector"))
      (node (ref "K3") (pin "-") (pinfunction "K_-") (pintype "passive"))
      (node (ref "P3") (pin "C") (pinfunction "C_C") (pintype "passive"))
    )
    (net (code "50") (name "SSR3-3V3") (class "Default")
      (node (ref "IC1") (pin "3") (pinfunction "I3_3") (pintype "input"))
      (node (ref "RN100") (pin "6") (pinfunction "2_6") (pintype "passive"))
      (node (ref "U$1") (pin "IO19") (pinfunction "IO19_IO19") (pintype "bidirectional"))
    )
    (net (code "51") (name "SSR4") (class "Default")
      (node (ref "IC1") (pin "15") (pinfunction "O4_15") (pintype "open_collector"))
      (node (ref "K4") (pin "-") (pinfunction "K_-") (pintype "passive"))
      (node (ref "P4") (pin "C") (pinfunction "C_C") (pintype "passive"))
    )
    (net (code "52") (name "SSR4-3V3") (class "Default")
      (node (ref "IC1") (pin "4") (pinfunction "I4_4") (pintype "input"))
      (node (ref "RN100") (pin "5") (pinfunction "2_5") (pintype "passive"))
      (node (ref "U$1") (pin "IO23") (pinfunction "IO23_IO23") (pintype "bidirectional"))
    )
    (net (code "53") (name "SSR5") (class "Default")
      (node (ref "IC1") (pin "14") (pinfunction "O5_14") (pintype "open_collector"))
      (node (ref "K5") (pin "-") (pinfunction "K_-") (pintype "passive"))
      (node (ref "P5") (pin "C") (pinfunction "C_C") (pintype "passive"))
    )
    (net (code "54") (name "SSR5-3V3") (class "Default")
      (node (ref "IC1") (pin "5") (pinfunction "I5_5") (pintype "input"))
      (node (ref "RN101") (pin "8") (pinfunction "2_8") (pintype "passive"))
      (node (ref "U$1") (pin "IO17") (pinfunction "IO17_IO17") (pintype "bidirectional"))
    )
    (net (code "55") (name "SSR6") (class "Default")
      (node (ref "IC1") (pin "13") (pinfunction "O6_13") (pintype "open_collector"))
      (node (ref "K6") (pin "-") (pinfunction "K_-") (pintype "passive"))
      (node (ref "P6") (pin "C") (pinfunction "C_C") (pintype "passive"))
    )
    (net (code "56") (name "SSR6-3V3") (class "Default")
      (node (ref "IC1") (pin "6") (pinfunction "I6_6") (pintype "input"))
      (node (ref "RN101") (pin "7") (pinfunction "2_7") (pintype "passive"))
      (node (ref "U$1") (pin "IO16") (pinfunction "IO16_IO16") (pintype "bidirectional"))
    )
    (net (code "57") (name "SSR7") (class "Default")
      (node (ref "IC1") (pin "12") (pinfunction "O7_12") (pintype "open_collector"))
      (node (ref "K7") (pin "-") (pinfunction "K_-") (pintype "passive"))
      (node (ref "P7") (pin "C") (pinfunction "C_C") (pintype "passive"))
    )
    (net (code "58") (name "SSR7-3V3") (class "Default")
      (node (ref "IC1") (pin "7") (pinfunction "I7_7") (pintype "input"))
      (node (ref "RN101") (pin "6") (pinfunction "2_6") (pintype "passive"))
      (node (ref "U$1") (pin "IO27") (pinfunction "IO27_IO27") (pintype "bidirectional"))
    )
    (net (code "59") (name "SSR8") (class "Default")
      (node (ref "IC1") (pin "11") (pinfunction "O8_11") (pintype "open_collector"))
      (node (ref "K8") (pin "-") (pinfunction "K_-") (pintype "passive"))
      (node (ref "P8") (pin "C") (pinfunction "C_C") (pintype "passive"))
    )
    (net (code "60") (name "SSR8-3V3") (class "Default")
      (node (ref "IC1") (pin "8") (pinfunction "I8_8") (pintype "input"))
      (node (ref "RN101") (pin "5") (pinfunction "2_5") (pintype "passive"))
      (node (ref "U$1") (pin "IO25") (pinfunction "IO25_IO25") (pintype "bidirectional"))
    )
    (net (code "61") (name "SSROUT-1") (class "Default")
      (node (ref "J5") (pin "2") (pinfunction "2_2") (pintype "passive"))
      (node (ref "K1") (pin "O2") (pinfunction "DS1_O2") (pintype "passive"))
    )
    (net (code "62") (name "SSROUT-2") (class "Default")
      (node (ref "J6") (pin "2") (pinfunction "2_2") (pintype "passive"))
      (node (ref "K2") (pin "O2") (pinfunction "DS1_O2") (pintype "passive"))
    )
    (net (code "63") (name "SSROUT-3") (class "Default")
      (node (ref "J7") (pin "2") (pinfunction "2_2") (pintype "passive"))
      (node (ref "K3") (pin "O2") (pinfunction "DS1_O2") (pintype "passive"))
    )
    (net (code "64") (name "SSROUT-4") (class "Default")
      (node (ref "J8") (pin "2") (pinfunction "2_2") (pintype "passive"))
      (node (ref "K4") (pin "O2") (pinfunction "DS1_O2") (pintype "passive"))
    )
    (net (code "65") (name "SSROUT-5") (class "Default")
      (node (ref "J9") (pin "2") (pinfunction "2_2") (pintype "passive"))
      (node (ref "K5") (pin "O2") (pinfunction "DS1_O2") (pintype "passive"))
    )
    (net (code "66") (name "SSROUT-6") (class "Default")
      (node (ref "J10") (pin "2") (pinfunction "2_2") (pintype "passive"))
      (node (ref "K6") (pin "O2") (pinfunction "DS1_O2") (pintype "passive"))
    )
    (net (code "67") (name "SSROUT-7") (class "Default")
      (node (ref "J11") (pin "2") (pinfunction "2_2") (pintype "passive"))
      (node (ref "K7") (pin "O2") (pinfunction "DS1_O2") (pintype "passive"))
    )
    (net (code "68") (name "SSROUT-8") (class "Default")
      (node (ref "J12") (pin "2") (pinfunction "2_2") (pintype "passive"))
      (node (ref "K8") (pin "O2") (pinfunction "DS1_O2") (pintype "passive"))
    )
    (net (code "69") (name "TEMP") (class "Default")
      (node (ref "JP1") (pin "2") (pinfunction "2_2") (pintype "passive"))
      (node (ref "U$1") (pin "IO2") (pinfunction "IO2_IO2") (pintype "bidirectional"))
    )
    (net (code "70") (name "TEMP-JP") (class "Default")
      (node (ref "JP1") (pin "1") (pinfunction "1_1") (pintype "passive"))
      (node (ref "R5") (pin "1") (pinfunction "1_1") (pintype "passive"))
      (node (ref "U1") (pin "2") (pinfunction "DQ_2") (pintype "bidirectional"))
    )
    (net (code "71") (name "VSSR") (class "Default")
      (node (ref "C10") (pin "2") (pinfunction "2_2") (pintype "passive"))
      (node (ref "C6") (pin "1") (pinfunction "1_1") (pintype "passive"))
      (node (ref "IC1") (pin "10") (pinfunction "CD+_10") (pintype "passive"))
      (node (ref "JP100") (pin "2") (pinfunction "2_2") (pintype "passive"))
      (node (ref "K1") (pin "+") (pinfunction "A_+") (pintype "passive"))
      (node (ref "K2") (pin "+") (pinfunction "A_+") (pintype "passive"))
      (node (ref "K3") (pin "+") (pinfunction "A_+") (pintype "passive"))
      (node (ref "K4") (pin "+") (pinfunction "A_+") (pintype "passive"))
      (node (ref "K5") (pin "+") (pinfunction "A_+") (pintype "passive"))
      (node (ref "K6") (pin "+") (pinfunction "A_+") (pintype "passive"))
      (node (ref "K7") (pin "+") (pinfunction "A_+") (pintype "passive"))
      (node (ref "K8") (pin "+") (pinfunction "A_+") (pintype "passive"))
    )
    (net (code "72") (name "ZEROSIGNAL") (class "Default")
      (node (ref "R14") (pin "1") (pinfunction "1_1") (pintype "passive"))
      (node (ref "U$1") (pin "IO33") (pinfunction "IO33_IO33") (pintype "bidirectional"))
      (node (ref "U2") (pin "4") (pinfunction "Y_4") (pintype "output"))
    )
    (net (code "73") (name "ZEROSIGNALRAW") (class "Default")
      (node (ref "JP2") (pin "1") (pinfunction "1_1") (pintype "passive"))
      (node (ref "OK100") (pin "4") (pinfunction "COL_4") (pintype "passive"))
      (node (ref "OK101") (pin "4") (pinfunction "COL_4") (pintype "passive"))
      (node (ref "R109") (pin "1") (pinfunction "1_1") (pintype "passive"))
      (node (ref "U2") (pin "2") (pinfunction "A_2") (pintype "input"))
    )
    (net (code "74") (name "unconnected-(D4-DO-Pad2)") (class "Default")
      (node (ref "D4") (pin "2") (pinfunction "DO_2") (pintype "bidirectional"))
    )
    (net (code "75") (name "unconnected-(U$1-IO06-PadCLK)") (class "Default")
      (node (ref "U$1") (pin "CLK") (pinfunction "IO06_CLK") (pintype "bidirectional"))
    )
    (net (code "76") (name "unconnected-(U$1-IO07-PadSD0)") (class "Default")
      (node (ref "U$1") (pin "SD0") (pinfunction "IO07_SD0") (pintype "bidirectional"))
    )
    (net (code "77") (name "unconnected-(U$1-IO08-PadSD1)") (class "Default")
      (node (ref "U$1") (pin "SD1") (pinfunction "IO08_SD1") (pintype "bidirectional"))
    )
    (net (code "78") (name "unconnected-(U$1-IO09-PadSD2)") (class "Default")
      (node (ref "U$1") (pin "SD2") (pinfunction "IO09_SD2") (pintype "bidirectional"))
    )
    (net (code "79") (name "unconnected-(U$1-IO10-PadSD3)") (class "Default")
      (node (ref "U$1") (pin "SD3") (pinfunction "IO10_SD3") (pintype "bidirectional"))
    )
    (net (code "80") (name "unconnected-(U$1-IO11-PadCMD)") (class "Default")
      (node (ref "U$1") (pin "CMD") (pinfunction "IO11_CMD") (pintype "bidirectional"))
    )
    (net (code "81") (name "unconnected-(U$1-IO12-PadTDI)") (class "Default")
      (node (ref "U$1") (pin "TDI") (pinfunction "IO12_TDI") (pintype "bidirectional"))
    )
    (net (code "82") (name "unconnected-(U$1-NC-PadNC2)") (class "Default")
      (node (ref "U$1") (pin "NC2") (pinfunction "NC_NC2") (pintype "bidirectional"))
    )
    (net (code "83") (name "unconnected-(U$1-PadNC)") (class "Default")
      (node (ref "U$1") (pin "NC") (pinfunction "NC_NC") (pintype "bidirectional"))
    )
    (net (code "84") (name "unconnected-(U$1-PadRST)") (class "Default")
      (node (ref "U$1") (pin "RST") (pinfunction "RST_RST") (pintype "bidirectional"))
    )
    (net (code "85") (name "unconnected-(U$1-PadRXD)") (class "Default")
      (node (ref "U$1") (pin "RXD") (pinfunction "RXD_RXD") (pintype "bidirectional"))
    )
    (net (code "86") (name "unconnected-(U$1-PadTXD)") (class "Default")
      (node (ref "U$1") (pin "TXD") (pinfunction "TXD_TXD") (pintype "bidirectional"))
    )
    (net (code "87") (name "unconnected-(U2-N.C-Pad1)") (class "Default")
      (node (ref "U2") (pin "1") (pinfunction "N.C_1") (pintype "bidirectional"))
    )
  )
)
